# schema1.net
KiCad netlist of a schematic drawn in EAGLE
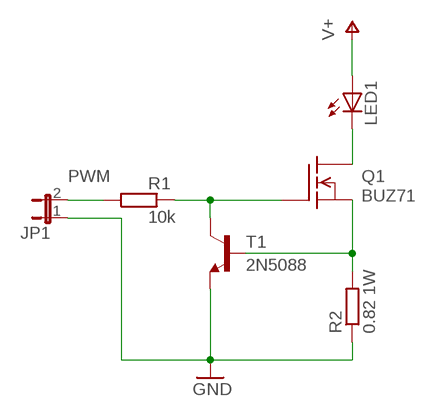
[diagram p0: schematic, sheet 1]

(export (version "E")
  (design (tool "Eeschema 10.0.6"))
  (components
    (comp (ref "JP1")
      (value "JUMPER-2PTH")
      (footprint "eagle-import:1X02")
      (libsource (lib "eagle-import") (part "JUMPER-2PTH"))
    )
    (comp (ref "LED1")
      (value "LED5MM")
      (footprint "eagle-import:LED5MM")
      (libsource (lib "eagle-import") (part "LED5MM"))
    )
    (comp (ref "Q1")
      (value "BUZ71")
      (footprint "eagle-import:TO220")
      (libsource (lib "eagle-import") (part "BUZ71"))
    )
    (comp (ref "R1")
      (value "10k")
      (footprint "eagle-import:0411_15")
      (libsource (lib "eagle-import") (part "R-EU_0411/15"))
    )
    (comp (ref "R2")
      (value "0.82 1W")
      (footprint "eagle-import:0411_15")
      (libsource (lib "eagle-import") (part "R-EU_0411/15"))
    )
    (comp (ref "T1")
      (value "2N5088")
      (footprint "eagle-import:TO92")
      (libsource (lib "eagle-import") (part "2N5088"))
    )
  )
  (nets
    (net (code "1") (name "/PWM") (class "Default")
      (node (ref "JP1") (pin "2") (pinfunction "2_2") (pintype "passive"))
      (node (ref "R1") (pin "1") (pinfunction "1_1") (pintype "passive"))
    )
    (net (code "2") (name "GND") (class "Default")
      (node (ref "JP1") (pin "1") (pinfunction "1_1") (pintype "passive"))
      (node (ref "R2") (pin "1") (pinfunction "1_1") (pintype "passive"))
      (node (ref "T1") (pin "3") (pinfunction "E_3") (pintype "passive"))
    )
    (net (code "3") (name "Net-(LED1-C)") (class "Default")
      (node (ref "LED1") (pin "K") (pinfunction "C_K") (pintype "passive"))
      (node (ref "Q1") (pin "2") (pinfunction "D_2") (pintype "passive"))
    )
    (net (code "4") (name "Net-(Q1-G)") (class "Default")
      (node (ref "Q1") (pin "1") (pinfunction "G_1") (pintype "passive"))
      (node (ref "R1") (pin "2") (pinfunction "2_2") (pintype "passive"))
      (node (ref "T1") (pin "1") (pinfunction "C_1") (pintype "passive"))
    )
    (net (code "5") (name "Net-(Q1-S)") (class "Default")
      (node (ref "Q1") (pin "3") (pinfunction "S_3") (pintype "passive"))
      (node (ref "R2") (pin "2") (pinfunction "2_2") (pintype "passive"))
      (node (ref "T1") (pin "2") (pinfunction "B_2") (pintype "passive"))
    )
    (net (code "6") (name "V+") (class "Default")
      (node (ref "LED1") (pin "A") (pinfunction "A_A") (pintype "passive"))
    )
  )
)
